# SAI_IO_Top_BOARD.net
KiCad netlist of a schematic drawn in EAGLE
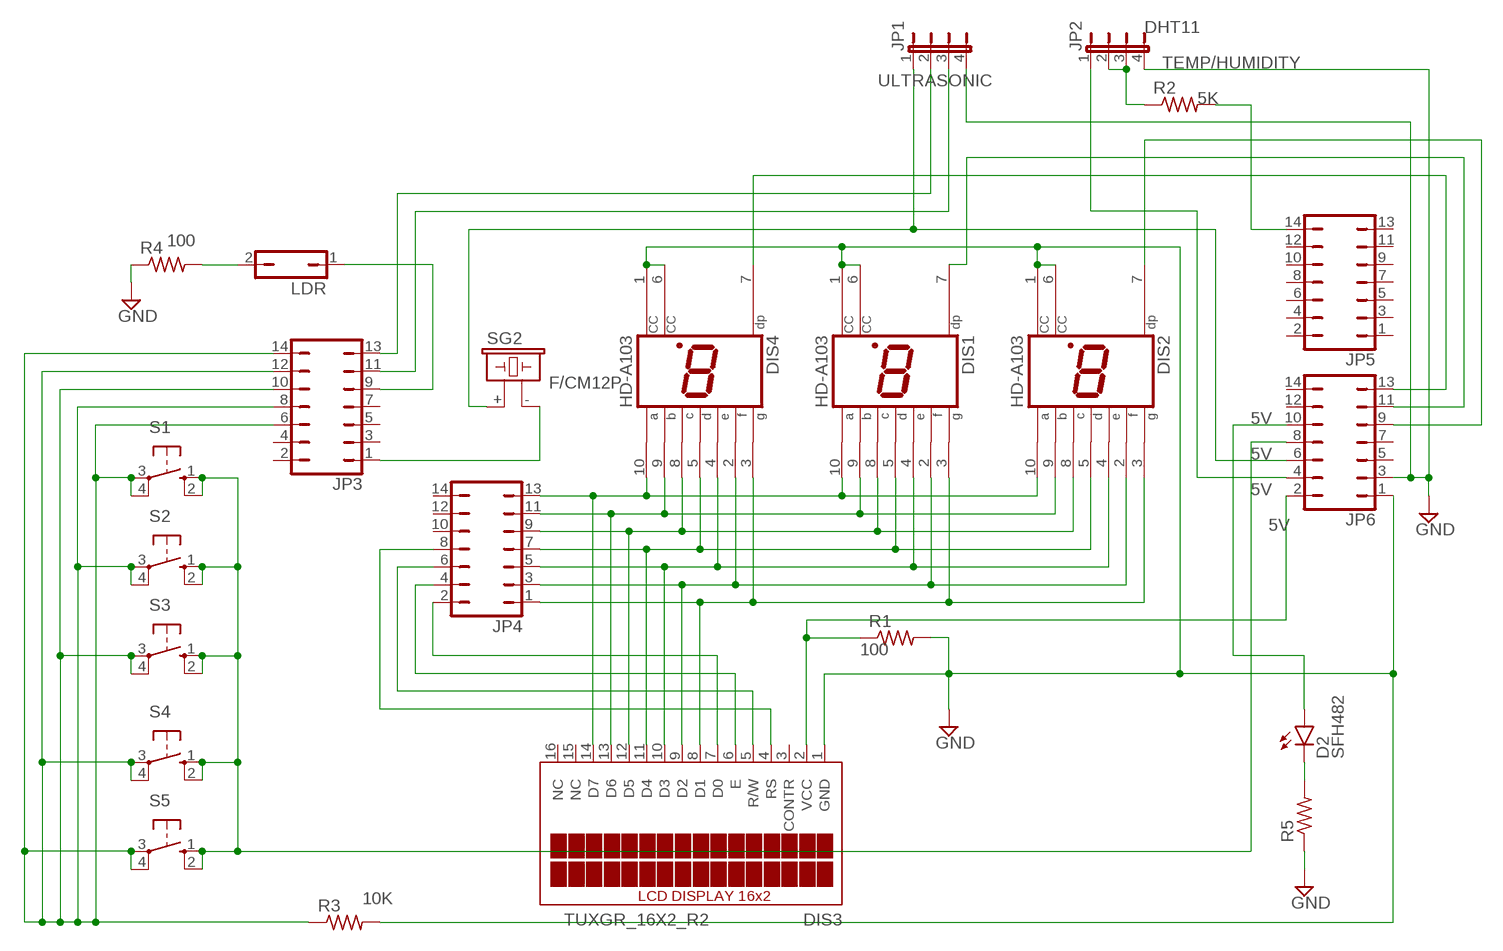
[diagram p0: schematic, sheet 1]

(export (version "E")
  (design (tool "Eeschema 10.0.6"))
  (components
    (comp (ref "D2")
      (value "SFH482")
      (footprint "eagle-import:SFH482")
      (libsource (lib "eagle-import") (part "SFH482"))
    )
    (comp (ref "DIS1")
      (value "HD-A103")
      (footprint "eagle-import:HDSP-A")
      (libsource (lib "eagle-import") (part "HD-A103"))
    )
    (comp (ref "DIS2")
      (value "HD-A103")
      (footprint "eagle-import:HDSP-A")
      (libsource (lib "eagle-import") (part "HD-A103"))
    )
    (comp (ref "DIS3")
      (value "TUXGR_16X2_R2")
      (footprint "eagle-import:TUXGR_16X2_R2")
      (libsource (lib "eagle-import") (part "TUXGR_16X2_R2"))
    )
    (comp (ref "DIS4")
      (value "HD-A103")
      (footprint "eagle-import:HDSP-A")
      (libsource (lib "eagle-import") (part "HD-A103"))
    )
    (comp (ref "JP1")
      (value "JP4E")
      (footprint "eagle-import:JP4")
      (libsource (lib "eagle-import") (part "JP4E"))
    )
    (comp (ref "JP2")
      (value "JP4E")
      (footprint "eagle-import:JP4")
      (libsource (lib "eagle-import") (part "JP4E"))
    )
    (comp (ref "JP3")
      (value "JP7Q")
      (footprint "eagle-import:JP7Q")
      (libsource (lib "eagle-import") (part "JP7Q"))
    )
    (comp (ref "JP4")
      (value "JP7Q")
      (footprint "eagle-import:JP7Q")
      (libsource (lib "eagle-import") (part "JP7Q"))
    )
    (comp (ref "JP5")
      (value "JP7Q")
      (footprint "eagle-import:JP7Q")
      (libsource (lib "eagle-import") (part "JP7Q"))
    )
    (comp (ref "JP6")
      (value "JP7Q")
      (footprint "eagle-import:JP7Q")
      (libsource (lib "eagle-import") (part "JP7Q"))
    )
    (comp (ref "LDR")
      (value "JP1Q")
      (footprint "eagle-import:JP1")
      (libsource (lib "eagle-import") (part "JP1Q"))
    )
    (comp (ref "R1")
      (value "R-US_0204/2V")
      (footprint "eagle-import:0204V")
      (libsource (lib "eagle-import") (part "R-US_0204/2V"))
    )
    (comp (ref "R2")
      (value "R-US_0204/2V")
      (footprint "eagle-import:0204V")
      (libsource (lib "eagle-import") (part "R-US_0204/2V"))
    )
    (comp (ref "R3")
      (value "R-US_0204/2V")
      (footprint "eagle-import:0204V")
      (libsource (lib "eagle-import") (part "R-US_0204/2V"))
    )
    (comp (ref "R4")
      (value "R-US_0204/2V")
      (footprint "eagle-import:0204V")
      (libsource (lib "eagle-import") (part "R-US_0204/2V"))
    )
    (comp (ref "R5")
      (value "R-US_0204/2V")
      (footprint "eagle-import:0204V")
      (libsource (lib "eagle-import") (part "R-US_0204/2V"))
    )
    (comp (ref "S1")
      (value "10-XX")
      (footprint "eagle-import:B3F-10XX")
      (fields (field (name "MPN") "B3F-1000"))
      (libsource (lib "eagle-import") (part "10-XX"))
    )
    (comp (ref "S2")
      (value "10-XX")
      (footprint "eagle-import:B3F-10XX")
      (fields (field (name "MPN") "B3F-1000"))
      (libsource (lib "eagle-import") (part "10-XX"))
    )
    (comp (ref "S3")
      (value "10-XX")
      (footprint "eagle-import:B3F-10XX")
      (fields (field (name "MPN") "B3F-1000"))
      (libsource (lib "eagle-import") (part "10-XX"))
    )
    (comp (ref "S4")
      (value "10-XX")
      (footprint "eagle-import:B3F-10XX")
      (fields (field (name "MPN") "B3F-1000"))
      (libsource (lib "eagle-import") (part "10-XX"))
    )
    (comp (ref "S5")
      (value "10-XX")
      (footprint "eagle-import:B3F-10XX")
      (fields (field (name "MPN") "B3F-1000"))
      (libsource (lib "eagle-import") (part "10-XX"))
    )
    (comp (ref "SG2")
      (value "F/CM12P")
      (footprint "eagle-import:F_CM12P")
      (libsource (lib "eagle-import") (part "F/CM12P"))
    )
  )
  (nets
    (net (code "1") (name "/5V") (class "Default")
      (node (ref "JP1") (pin "1") (pinfunction "1_1") (pintype "passive"))
      (node (ref "JP6") (pin "6") (pinfunction "6_6") (pintype "passive"))
      (node (ref "SG2") (pin "+") (pinfunction "1_+") (pintype "passive"))
    )
    (net (code "2") (name "GND") (class "Default")
      (node (ref "DIS1") (pin "1") (pinfunction "CC_1") (pintype "passive"))
      (node (ref "DIS1") (pin "6") (pinfunction "CC_6") (pintype "passive"))
      (node (ref "DIS2") (pin "1") (pinfunction "CC_1") (pintype "passive"))
      (node (ref "DIS2") (pin "6") (pinfunction "CC_6") (pintype "passive"))
      (node (ref "DIS3") (pin "1") (pinfunction "GND_1") (pintype "power_in"))
      (node (ref "DIS4") (pin "1") (pinfunction "CC_1") (pintype "passive"))
      (node (ref "DIS4") (pin "6") (pinfunction "CC_6") (pintype "passive"))
      (node (ref "JP1") (pin "4") (pinfunction "4_4") (pintype "passive"))
      (node (ref "JP2") (pin "4") (pinfunction "4_4") (pintype "passive"))
      (node (ref "JP6") (pin "1") (pinfunction "1_1") (pintype "passive"))
      (node (ref "JP6") (pin "3") (pinfunction "3_3") (pintype "passive"))
      (node (ref "R1") (pin "2") (pinfunction "2_2") (pintype "passive"))
      (node (ref "R3") (pin "2") (pinfunction "2_2") (pintype "passive"))
      (node (ref "R4") (pin "1") (pinfunction "1_1") (pintype "passive"))
      (node (ref "R5") (pin "1") (pinfunction "1_1") (pintype "passive"))
    )
    (net (code "3") (name "Net-(D2-C)") (class "Default")
      (node (ref "D2") (pin "K") (pinfunction "C_K") (pintype "passive"))
      (node (ref "R5") (pin "2") (pinfunction "2_2") (pintype "passive"))
    )
    (net (code "4") (name "Net-(D2-PadA)") (class "Default")
      (node (ref "D2") (pin "A") (pinfunction "A_A") (pintype "passive"))
      (node (ref "JP6") (pin "10") (pinfunction "10_10") (pintype "passive"))
    )
    (net (code "5") (name "Net-(DIS1-A)") (class "Default")
      (node (ref "DIS1") (pin "10") (pinfunction "A_10") (pintype "passive"))
      (node (ref "DIS2") (pin "10") (pinfunction "A_10") (pintype "passive"))
      (node (ref "DIS3") (pin "14") (pinfunction "D7_14") (pintype "input"))
      (node (ref "DIS4") (pin "10") (pinfunction "A_10") (pintype "passive"))
      (node (ref "JP4") (pin "13") (pinfunction "13_13") (pintype "passive"))
    )
    (net (code "6") (name "Net-(DIS1-B)") (class "Default")
      (node (ref "DIS1") (pin "9") (pinfunction "B_9") (pintype "passive"))
      (node (ref "DIS2") (pin "9") (pinfunction "B_9") (pintype "passive"))
      (node (ref "DIS3") (pin "13") (pinfunction "D6_13") (pintype "input"))
      (node (ref "DIS4") (pin "9") (pinfunction "B_9") (pintype "passive"))
      (node (ref "JP4") (pin "11") (pinfunction "11_11") (pintype "passive"))
    )
    (net (code "7") (name "Net-(DIS1-C)") (class "Default")
      (node (ref "DIS1") (pin "8") (pinfunction "C_8") (pintype "passive"))
      (node (ref "DIS2") (pin "8") (pinfunction "C_8") (pintype "passive"))
      (node (ref "DIS3") (pin "12") (pinfunction "D5_12") (pintype "input"))
      (node (ref "DIS4") (pin "8") (pinfunction "C_8") (pintype "passive"))
      (node (ref "JP4") (pin "9") (pinfunction "9_9") (pintype "passive"))
    )
    (net (code "8") (name "Net-(DIS1-D)") (class "Default")
      (node (ref "DIS1") (pin "5") (pinfunction "D_5") (pintype "passive"))
      (node (ref "DIS2") (pin "5") (pinfunction "D_5") (pintype "passive"))
      (node (ref "DIS3") (pin "11") (pinfunction "D4_11") (pintype "input"))
      (node (ref "DIS4") (pin "5") (pinfunction "D_5") (pintype "passive"))
      (node (ref "JP4") (pin "7") (pinfunction "7_7") (pintype "passive"))
    )
    (net (code "9") (name "Net-(DIS1-DP)") (class "Default")
      (node (ref "DIS1") (pin "7") (pinfunction "DP_7") (pintype "passive"))
      (node (ref "JP6") (pin "11") (pinfunction "11_11") (pintype "passive"))
    )
    (net (code "10") (name "Net-(DIS1-E)") (class "Default")
      (node (ref "DIS1") (pin "4") (pinfunction "E_4") (pintype "passive"))
      (node (ref "DIS2") (pin "4") (pinfunction "E_4") (pintype "passive"))
      (node (ref "DIS3") (pin "10") (pinfunction "D3_10") (pintype "input"))
      (node (ref "DIS4") (pin "4") (pinfunction "E_4") (pintype "passive"))
      (node (ref "JP4") (pin "5") (pinfunction "5_5") (pintype "passive"))
    )
    (net (code "11") (name "Net-(DIS1-F)") (class "Default")
      (node (ref "DIS1") (pin "2") (pinfunction "F_2") (pintype "passive"))
      (node (ref "DIS2") (pin "2") (pinfunction "F_2") (pintype "passive"))
      (node (ref "DIS3") (pin "9") (pinfunction "D2_9") (pintype "input"))
      (node (ref "DIS4") (pin "2") (pinfunction "F_2") (pintype "passive"))
      (node (ref "JP4") (pin "3") (pinfunction "3_3") (pintype "passive"))
    )
    (net (code "12") (name "Net-(DIS1-G)") (class "Default")
      (node (ref "DIS1") (pin "3") (pinfunction "G_3") (pintype "passive"))
      (node (ref "DIS2") (pin "3") (pinfunction "G_3") (pintype "passive"))
      (node (ref "DIS3") (pin "8") (pinfunction "D1_8") (pintype "input"))
      (node (ref "DIS4") (pin "3") (pinfunction "G_3") (pintype "passive"))
      (node (ref "JP4") (pin "1") (pinfunction "1_1") (pintype "passive"))
    )
    (net (code "13") (name "Net-(DIS2-DP)") (class "Default")
      (node (ref "DIS2") (pin "7") (pinfunction "DP_7") (pintype "passive"))
      (node (ref "JP6") (pin "9") (pinfunction "9_9") (pintype "passive"))
    )
    (net (code "14") (name "Net-(DIS3-D0)") (class "Default")
      (node (ref "DIS3") (pin "7") (pinfunction "D0_7") (pintype "input"))
      (node (ref "JP4") (pin "2") (pinfunction "2_2") (pintype "passive"))
    )
    (net (code "15") (name "Net-(DIS3-E)") (class "Default")
      (node (ref "DIS3") (pin "6") (pinfunction "E_6") (pintype "input"))
      (node (ref "JP4") (pin "4") (pinfunction "4_4") (pintype "passive"))
    )
    (net (code "16") (name "Net-(DIS3-RS)") (class "Default")
      (node (ref "DIS3") (pin "4") (pinfunction "RS_4") (pintype "input"))
      (node (ref "JP4") (pin "8") (pinfunction "8_8") (pintype "passive"))
    )
    (net (code "17") (name "Net-(DIS3-R{slash}W)") (class "Default")
      (node (ref "DIS3") (pin "5") (pinfunction "R/W_5") (pintype "input"))
      (node (ref "JP4") (pin "6") (pinfunction "6_6") (pintype "passive"))
    )
    (net (code "18") (name "Net-(DIS3-VCC)") (class "Default")
      (node (ref "DIS3") (pin "2") (pinfunction "VCC_2") (pintype "power_in"))
      (node (ref "JP6") (pin "2") (pinfunction "2_2") (pintype "passive"))
      (node (ref "R1") (pin "1") (pinfunction "1_1") (pintype "passive"))
    )
    (net (code "19") (name "Net-(DIS4-DP)") (class "Default")
      (node (ref "DIS4") (pin "7") (pinfunction "DP_7") (pintype "passive"))
      (node (ref "JP6") (pin "13") (pinfunction "13_13") (pintype "passive"))
    )
    (net (code "20") (name "Net-(JP1-Pad2)") (class "Default")
      (node (ref "JP1") (pin "2") (pinfunction "2_2") (pintype "passive"))
      (node (ref "JP3") (pin "13") (pinfunction "13_13") (pintype "passive"))
    )
    (net (code "21") (name "Net-(JP1-Pad3)") (class "Default")
      (node (ref "JP1") (pin "3") (pinfunction "3_3") (pintype "passive"))
      (node (ref "JP3") (pin "11") (pinfunction "11_11") (pintype "passive"))
    )
    (net (code "22") (name "Net-(JP2-Pad1)") (class "Default")
      (node (ref "JP2") (pin "1") (pinfunction "1_1") (pintype "passive"))
      (node (ref "JP6") (pin "4") (pinfunction "4_4") (pintype "passive"))
    )
    (net (code "23") (name "Net-(JP2-Pad2)") (class "Default")
      (node (ref "JP2") (pin "2") (pinfunction "2_2") (pintype "passive"))
      (node (ref "JP2") (pin "3") (pinfunction "3_3") (pintype "passive"))
      (node (ref "R2") (pin "1") (pinfunction "1_1") (pintype "passive"))
    )
    (net (code "24") (name "Net-(JP3-Pad9)") (class "Default")
      (node (ref "JP3") (pin "9") (pinfunction "9_9") (pintype "passive"))
      (node (ref "LDR") (pin "1") (pinfunction "1_1") (pintype "passive"))
    )
    (net (code "25") (name "Net-(JP5-Pad14)") (class "Default")
      (node (ref "JP5") (pin "14") (pinfunction "14_14") (pintype "passive"))
      (node (ref "R2") (pin "2") (pinfunction "2_2") (pintype "passive"))
    )
    (net (code "26") (name "Net-(LDR-Pad2)") (class "Default")
      (node (ref "LDR") (pin "2") (pinfunction "2_2") (pintype "passive"))
      (node (ref "R4") (pin "2") (pinfunction "2_2") (pintype "passive"))
    )
    (net (code "27") (name "Net-(S1-P)") (class "Default")
      (node (ref "JP3") (pin "10") (pinfunction "10_10") (pintype "passive"))
      (node (ref "JP3") (pin "12") (pinfunction "12_12") (pintype "passive"))
      (node (ref "JP3") (pin "14") (pinfunction "14_14") (pintype "passive"))
      (node (ref "JP3") (pin "6") (pinfunction "6_6") (pintype "passive"))
      (node (ref "JP3") (pin "8") (pinfunction "8_8") (pintype "passive"))
      (node (ref "R3") (pin "1") (pinfunction "1_1") (pintype "passive"))
      (node (ref "S1") (pin "3") (pinfunction "P_3") (pintype "passive"))
      (node (ref "S1") (pin "4") (pinfunction "P1_4") (pintype "passive"))
      (node (ref "S2") (pin "3") (pinfunction "P_3") (pintype "passive"))
      (node (ref "S2") (pin "4") (pinfunction "P1_4") (pintype "passive"))
      (node (ref "S3") (pin "3") (pinfunction "P_3") (pintype "passive"))
      (node (ref "S3") (pin "4") (pinfunction "P1_4") (pintype "passive"))
      (node (ref "S4") (pin "3") (pinfunction "P_3") (pintype "passive"))
      (node (ref "S4") (pin "4") (pinfunction "P1_4") (pintype "passive"))
      (node (ref "S5") (pin "3") (pinfunction "P_3") (pintype "passive"))
      (node (ref "S5") (pin "4") (pinfunction "P1_4") (pintype "passive"))
    )
    (net (code "28") (name "Net-(S1-S)") (class "Default")
      (node (ref "JP6") (pin "8") (pinfunction "8_8") (pintype "passive"))
      (node (ref "S1") (pin "1") (pinfunction "S_1") (pintype "passive"))
      (node (ref "S1") (pin "2") (pinfunction "S1_2") (pintype "passive"))
      (node (ref "S2") (pin "1") (pinfunction "S_1") (pintype "passive"))
      (node (ref "S2") (pin "2") (pinfunction "S1_2") (pintype "passive"))
      (node (ref "S3") (pin "1") (pinfunction "S_1") (pintype "passive"))
      (node (ref "S3") (pin "2") (pinfunction "S1_2") (pintype "passive"))
      (node (ref "S4") (pin "1") (pinfunction "S_1") (pintype "passive"))
      (node (ref "S4") (pin "2") (pinfunction "S1_2") (pintype "passive"))
      (node (ref "S5") (pin "1") (pinfunction "S_1") (pintype "passive"))
      (node (ref "S5") (pin "2") (pinfunction "S1_2") (pintype "passive"))
    )
    (net (code "29") (name "Net-(SG2-2)") (class "Default")
      (node (ref "JP3") (pin "1") (pinfunction "1_1") (pintype "passive"))
      (node (ref "SG2") (pin "-") (pinfunction "2_-") (pintype "passive"))
    )
    (net (code "30") (name "unconnected-(DIS3-CONTR-Pad3)") (class "Default")
      (node (ref "DIS3") (pin "3") (pinfunction "CONTR_3") (pintype "input"))
    )
    (net (code "31") (name "unconnected-(DIS3-NC-Pad15)") (class "Default")
      (node (ref "DIS3") (pin "15") (pinfunction "NC_15") (pintype "no_connect"))
    )
    (net (code "32") (name "unconnected-(DIS3-NC-Pad16)") (class "Default")
      (node (ref "DIS3") (pin "16") (pinfunction "NC_16") (pintype "no_connect"))
    )
    (net (code "33") (name "unconnected-(JP3-Pad2)") (class "Default")
      (node (ref "JP3") (pin "2") (pinfunction "2_2") (pintype "passive"))
    )
    (net (code "34") (name "unconnected-(JP3-Pad3)") (class "Default")
      (node (ref "JP3") (pin "3") (pinfunction "3_3") (pintype "passive"))
    )
    (net (code "35") (name "unconnected-(JP3-Pad4)") (class "Default")
      (node (ref "JP3") (pin "4") (pinfunction "4_4") (pintype "passive"))
    )
    (net (code "36") (name "unconnected-(JP3-Pad5)") (class "Default")
      (node (ref "JP3") (pin "5") (pinfunction "5_5") (pintype "passive"))
    )
    (net (code "37") (name "unconnected-(JP3-Pad7)") (class "Default")
      (node (ref "JP3") (pin "7") (pinfunction "7_7") (pintype "passive"))
    )
    (net (code "38") (name "unconnected-(JP4-Pad10)") (class "Default")
      (node (ref "JP4") (pin "10") (pinfunction "10_10") (pintype "passive"))
    )
    (net (code "39") (name "unconnected-(JP4-Pad12)") (class "Default")
      (node (ref "JP4") (pin "12") (pinfunction "12_12") (pintype "passive"))
    )
    (net (code "40") (name "unconnected-(JP4-Pad14)") (class "Default")
      (node (ref "JP4") (pin "14") (pinfunction "14_14") (pintype "passive"))
    )
    (net (code "41") (name "unconnected-(JP5-Pad1)") (class "Default")
      (node (ref "JP5") (pin "1") (pinfunction "1_1") (pintype "passive"))
    )
    (net (code "42") (name "unconnected-(JP5-Pad2)") (class "Default")
      (node (ref "JP5") (pin "2") (pinfunction "2_2") (pintype "passive"))
    )
    (net (code "43") (name "unconnected-(JP5-Pad3)") (class "Default")
      (node (ref "JP5") (pin "3") (pinfunction "3_3") (pintype "passive"))
    )
    (net (code "44") (name "unconnected-(JP5-Pad4)") (class "Default")
      (node (ref "JP5") (pin "4") (pinfunction "4_4") (pintype "passive"))
    )
    (net (code "45") (name "unconnected-(JP5-Pad5)") (class "Default")
      (node (ref "JP5") (pin "5") (pinfunction "5_5") (pintype "passive"))
    )
    (net (code "46") (name "unconnected-(JP5-Pad6)") (class "Default")
      (node (ref "JP5") (pin "6") (pinfunction "6_6") (pintype "passive"))
    )
    (net (code "47") (name "unconnected-(JP5-Pad7)") (class "Default")
      (node (ref "JP5") (pin "7") (pinfunction "7_7") (pintype "passive"))
    )
    (net (code "48") (name "unconnected-(JP5-Pad8)") (class "Default")
      (node (ref "JP5") (pin "8") (pinfunction "8_8") (pintype "passive"))
    )
    (net (code "49") (name "unconnected-(JP5-Pad9)") (class "Default")
      (node (ref "JP5") (pin "9") (pinfunction "9_9") (pintype "passive"))
    )
    (net (code "50") (name "unconnected-(JP5-Pad10)") (class "Default")
      (node (ref "JP5") (pin "10") (pinfunction "10_10") (pintype "passive"))
    )
    (net (code "51") (name "unconnected-(JP5-Pad11)") (class "Default")
      (node (ref "JP5") (pin "11") (pinfunction "11_11") (pintype "passive"))
    )
    (net (code "52") (name "unconnected-(JP5-Pad12)") (class "Default")
      (node (ref "JP5") (pin "12") (pinfunction "12_12") (pintype "passive"))
    )
    (net (code "53") (name "unconnected-(JP5-Pad13)") (class "Default")
      (node (ref "JP5") (pin "13") (pinfunction "13_13") (pintype "passive"))
    )
    (net (code "54") (name "unconnected-(JP6-Pad5)") (class "Default")
      (node (ref "JP6") (pin "5") (pinfunction "5_5") (pintype "passive"))
    )
    (net (code "55") (name "unconnected-(JP6-Pad7)") (class "Default")
      (node (ref "JP6") (pin "7") (pinfunction "7_7") (pintype "passive"))
    )
    (net (code "56") (name "unconnected-(JP6-Pad12)") (class "Default")
      (node (ref "JP6") (pin "12") (pinfunction "12_12") (pintype "passive"))
    )
    (net (code "57") (name "unconnected-(JP6-Pad14)") (class "Default")
      (node (ref "JP6") (pin "14") (pinfunction "14_14") (pintype "passive"))
    )
  )
)
